# signal3.net
KiCad netlist of a schematic drawn in Altium Designer
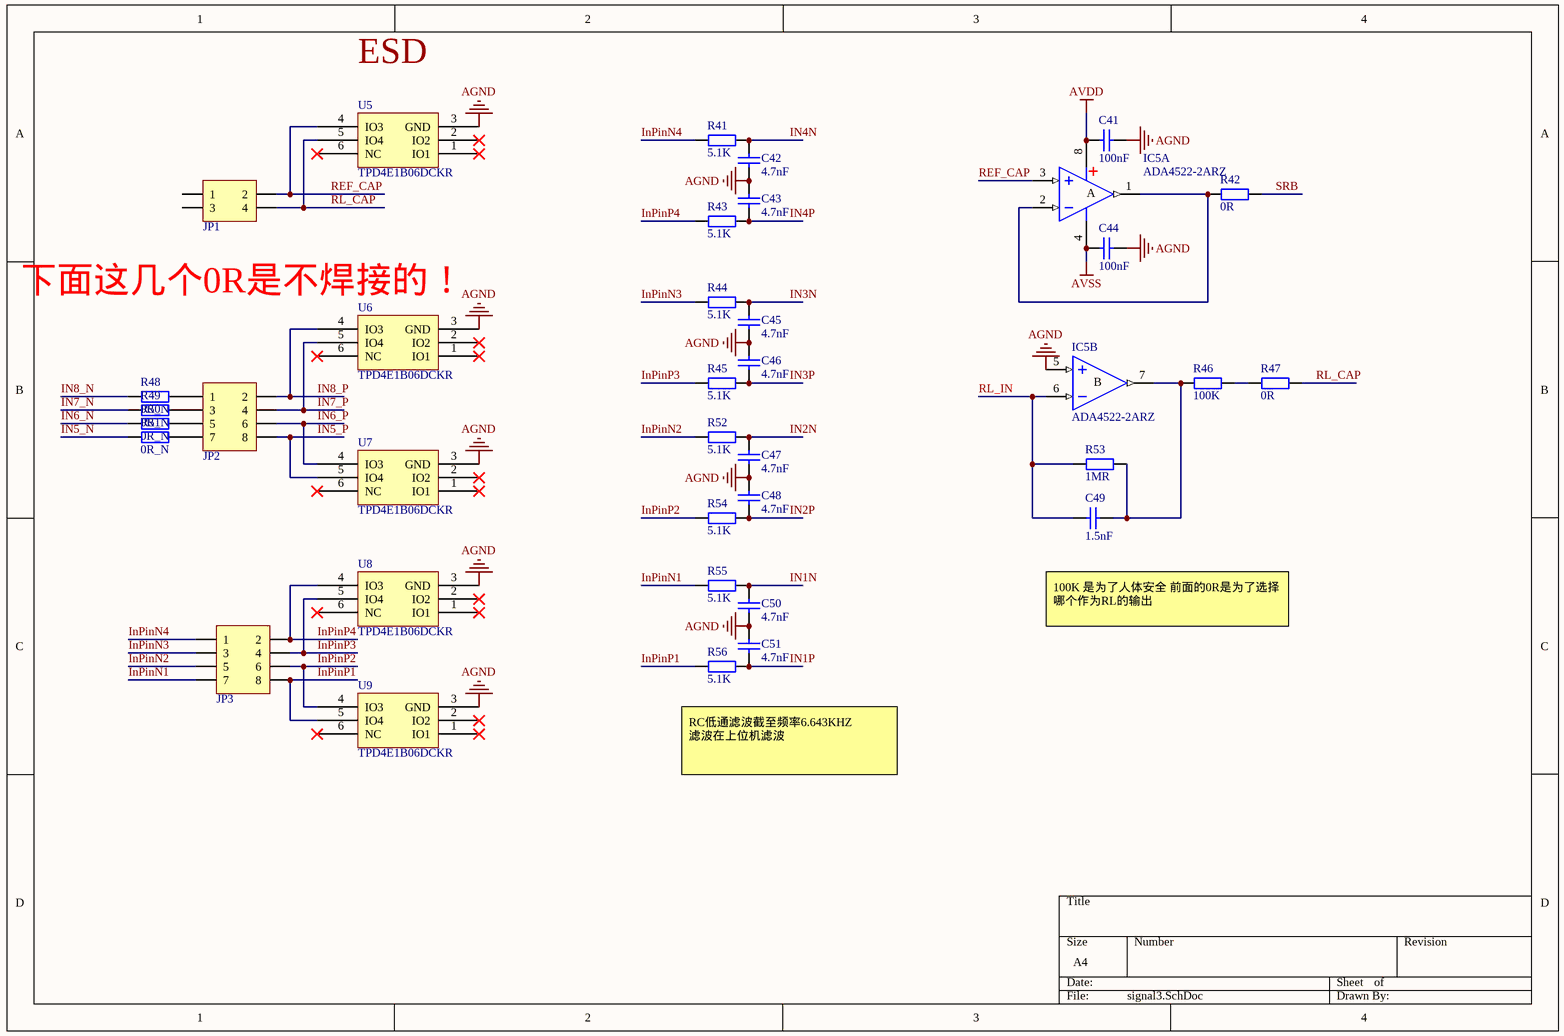
[diagram p0: signal3.SchDoc]

(export (version "E")
  (design (tool "Eeschema 10.0.6"))
  (components
    (comp (ref "C41")
      (value "100nF")
      (footprint "C0603_L")
      (description "贴片电容/MLCC电容")
      (libsource (lib "0.1 - 电阻-电容-电感-保险丝-晶振-晶体-磁珠-电位器-法拉电容-馈通电容") (part "C"))
    )
    (comp (ref "C42")
      (value "4.7nF")
      (footprint "C0603_L")
      (description "贴片电容/MLCC电容")
      (libsource (lib "0.1 - 电阻-电容-电感-保险丝-晶振-晶体-磁珠-电位器-法拉电容-馈通电容") (part "C"))
    )
    (comp (ref "C43")
      (value "4.7nF")
      (footprint "C0603_L")
      (description "贴片电容/MLCC电容")
      (libsource (lib "0.1 - 电阻-电容-电感-保险丝-晶振-晶体-磁珠-电位器-法拉电容-馈通电容") (part "C"))
    )
    (comp (ref "C44")
      (value "100nF")
      (footprint "C0603_L")
      (description "贴片电容/MLCC电容")
      (libsource (lib "0.1 - 电阻-电容-电感-保险丝-晶振-晶体-磁珠-电位器-法拉电容-馈通电容") (part "C"))
    )
    (comp (ref "C45")
      (value "4.7nF")
      (footprint "C0603_L")
      (description "贴片电容/MLCC电容")
      (libsource (lib "0.1 - 电阻-电容-电感-保险丝-晶振-晶体-磁珠-电位器-法拉电容-馈通电容") (part "C"))
    )
    (comp (ref "C46")
      (value "4.7nF")
      (footprint "C0603_L")
      (description "贴片电容/MLCC电容")
      (libsource (lib "0.1 - 电阻-电容-电感-保险丝-晶振-晶体-磁珠-电位器-法拉电容-馈通电容") (part "C"))
    )
    (comp (ref "C47")
      (value "4.7nF")
      (footprint "C0603_L")
      (description "贴片电容/MLCC电容")
      (libsource (lib "0.1 - 电阻-电容-电感-保险丝-晶振-晶体-磁珠-电位器-法拉电容-馈通电容") (part "C"))
    )
    (comp (ref "C48")
      (value "4.7nF")
      (footprint "C0603_L")
      (description "贴片电容/MLCC电容")
      (libsource (lib "0.1 - 电阻-电容-电感-保险丝-晶振-晶体-磁珠-电位器-法拉电容-馈通电容") (part "C"))
    )
    (comp (ref "C49")
      (value "1.5nF")
      (footprint "C0603_L")
      (description "贴片电容/MLCC电容")
      (libsource (lib "0.1 - 电阻-电容-电感-保险丝-晶振-晶体-磁珠-电位器-法拉电容-馈通电容") (part "C"))
    )
    (comp (ref "C50")
      (value "4.7nF")
      (footprint "C0603_L")
      (description "贴片电容/MLCC电容")
      (libsource (lib "0.1 - 电阻-电容-电感-保险丝-晶振-晶体-磁珠-电位器-法拉电容-馈通电容") (part "C"))
    )
    (comp (ref "C51")
      (value "4.7nF")
      (footprint "C0603_L")
      (description "贴片电容/MLCC电容")
      (libsource (lib "0.1 - 电阻-电容-电感-保险丝-晶振-晶体-磁珠-电位器-法拉电容-馈通电容") (part "C"))
    )
    (comp (ref "IC5")
      (value "ADA4522-2ARZ")
      (footprint "SOIC-8")
      (description "双通道55V、EMI增强型、零漂移、超低噪声、RRO运算放大器")
      (libsource (lib "HT") (part "ADA4522-2ARZ"))
    )
    (comp (ref "JP1")
      (value "Header2X2")
      (footprint "HDR2.54-WI-2x2P")
      (description "2*2P接插件")
      (libsource (lib "5.5 - 2.54mm连接器(KF2EDGK_XH2.54_2.54排针排母)") (part "Header 2X2"))
    )
    (comp (ref "JP2")
      (value "Header 4X2")
      (footprint "HDR2.54-WI-2x4P")
      (description "4*2P接插件")
      (libsource (lib "5.5 - 2.54mm连接器(KF2EDGK_XH2.54_2.54排针排母)") (part "Header 4X2"))
    )
    (comp (ref "JP3")
      (value "Header 4X2")
      (footprint "HDR2.54-WI-2x4P")
      (description "4*2P接插件")
      (libsource (lib "5.5 - 2.54mm连接器(KF2EDGK_XH2.54_2.54排针排母)") (part "Header 4X2"))
    )
    (comp (ref "R41")
      (value "5.1K")
      (footprint "R0603_L")
      (description "贴片电阻")
      (libsource (lib "0.1 - 电阻-电容-电感-保险丝-晶振-晶体-磁珠-电位器-法拉电容-馈通电容") (part "R"))
    )
    (comp (ref "R42")
      (value "0R")
      (footprint "R0603_L")
      (description "贴片电阻")
      (libsource (lib "0.1 - 电阻-电容-电感-保险丝-晶振-晶体-磁珠-电位器-法拉电容-馈通电容") (part "R"))
    )
    (comp (ref "R43")
      (value "5.1K")
      (footprint "R0603_L")
      (description "贴片电阻")
      (libsource (lib "0.1 - 电阻-电容-电感-保险丝-晶振-晶体-磁珠-电位器-法拉电容-馈通电容") (part "R"))
    )
    (comp (ref "R44")
      (value "5.1K")
      (footprint "R0603_L")
      (description "贴片电阻")
      (libsource (lib "0.1 - 电阻-电容-电感-保险丝-晶振-晶体-磁珠-电位器-法拉电容-馈通电容") (part "R"))
    )
    (comp (ref "R45")
      (value "5.1K")
      (footprint "R0603_L")
      (description "贴片电阻")
      (libsource (lib "0.1 - 电阻-电容-电感-保险丝-晶振-晶体-磁珠-电位器-法拉电容-馈通电容") (part "R"))
    )
    (comp (ref "R46")
      (value "100K")
      (footprint "R0603_L")
      (description "贴片电阻")
      (libsource (lib "0.1 - 电阻-电容-电感-保险丝-晶振-晶体-磁珠-电位器-法拉电容-馈通电容") (part "R"))
    )
    (comp (ref "R47")
      (value "0R")
      (footprint "R0603_L")
      (description "贴片电阻")
      (libsource (lib "0.1 - 电阻-电容-电感-保险丝-晶振-晶体-磁珠-电位器-法拉电容-馈通电容") (part "R"))
    )
    (comp (ref "R48")
      (value "0R_N")
      (footprint "R0603_L")
      (description "贴片电阻")
      (libsource (lib "0.1 - 电阻-电容-电感-保险丝-晶振-晶体-磁珠-电位器-法拉电容-馈通电容") (part "R"))
    )
    (comp (ref "R49")
      (value "0R_N")
      (footprint "R0603_L")
      (description "贴片电阻")
      (libsource (lib "0.1 - 电阻-电容-电感-保险丝-晶振-晶体-磁珠-电位器-法拉电容-馈通电容") (part "R"))
    )
    (comp (ref "R50")
      (value "0R_N")
      (footprint "R0603_L")
      (description "贴片电阻")
      (libsource (lib "0.1 - 电阻-电容-电感-保险丝-晶振-晶体-磁珠-电位器-法拉电容-馈通电容") (part "R"))
    )
    (comp (ref "R51")
      (value "0R_N")
      (footprint "R0603_L")
      (description "贴片电阻")
      (libsource (lib "0.1 - 电阻-电容-电感-保险丝-晶振-晶体-磁珠-电位器-法拉电容-馈通电容") (part "R"))
    )
    (comp (ref "R52")
      (value "5.1K")
      (footprint "R0603_L")
      (description "贴片电阻")
      (libsource (lib "0.1 - 电阻-电容-电感-保险丝-晶振-晶体-磁珠-电位器-法拉电容-馈通电容") (part "R"))
    )
    (comp (ref "R53")
      (value "1MR")
      (footprint "R0603_L")
      (description "贴片电阻")
      (libsource (lib "0.1 - 电阻-电容-电感-保险丝-晶振-晶体-磁珠-电位器-法拉电容-馈通电容") (part "R"))
    )
    (comp (ref "R54")
      (value "5.1K")
      (footprint "R0603_L")
      (description "贴片电阻")
      (libsource (lib "0.1 - 电阻-电容-电感-保险丝-晶振-晶体-磁珠-电位器-法拉电容-馈通电容") (part "R"))
    )
    (comp (ref "R55")
      (value "5.1K")
      (footprint "R0603_L")
      (description "贴片电阻")
      (libsource (lib "0.1 - 电阻-电容-电感-保险丝-晶振-晶体-磁珠-电位器-法拉电容-馈通电容") (part "R"))
    )
    (comp (ref "R56")
      (value "5.1K")
      (footprint "R0603_L")
      (description "贴片电阻")
      (libsource (lib "0.1 - 电阻-电容-电感-保险丝-晶振-晶体-磁珠-电位器-法拉电容-馈通电容") (part "R"))
    )
    (comp (ref "U5")
      (value "TPD4E1B06DCKR")
      (footprint "SOT363_N")
      (description "具有 0.5nA 最大泄漏电流的四路 0.7pF、±5.5V、±12kV ESD 保护二极管")
      (libsource (lib "HT") (part "TPD4E1B06DCKR"))
    )
    (comp (ref "U6")
      (value "TPD4E1B06DCKR")
      (footprint "SOT363_N")
      (description "具有 0.5nA 最大泄漏电流的四路 0.7pF、±5.5V、±12kV ESD 保护二极管")
      (libsource (lib "HT") (part "TPD4E1B06DCKR"))
    )
    (comp (ref "U7")
      (value "TPD4E1B06DCKR")
      (footprint "SOT363_N")
      (description "具有 0.5nA 最大泄漏电流的四路 0.7pF、±5.5V、±12kV ESD 保护二极管")
      (libsource (lib "HT") (part "TPD4E1B06DCKR"))
    )
    (comp (ref "U8")
      (value "TPD4E1B06DCKR")
      (footprint "SOT363_N")
      (description "具有 0.5nA 最大泄漏电流的四路 0.7pF、±5.5V、±12kV ESD 保护二极管")
      (libsource (lib "HT") (part "TPD4E1B06DCKR"))
    )
    (comp (ref "U9")
      (value "TPD4E1B06DCKR")
      (footprint "SOT363_N")
      (description "具有 0.5nA 最大泄漏电流的四路 0.7pF、±5.5V、±12kV ESD 保护二极管")
      (libsource (lib "HT") (part "TPD4E1B06DCKR"))
    )
  )
  (nets
    (net (code "1") (name "/IN1N") (class "Default")
      (node (ref "C50") (pin "2") (pinfunction "2_2") (pintype "passive"))
      (node (ref "R55") (pin "2") (pinfunction "2_2") (pintype "passive"))
    )
    (net (code "2") (name "/IN1P") (class "Default")
      (node (ref "C51") (pin "1") (pinfunction "1_1") (pintype "passive"))
      (node (ref "R56") (pin "2") (pinfunction "2_2") (pintype "passive"))
    )
    (net (code "3") (name "/IN2N") (class "Default")
      (node (ref "C47") (pin "2") (pinfunction "2_2") (pintype "passive"))
      (node (ref "R52") (pin "2") (pinfunction "2_2") (pintype "passive"))
    )
    (net (code "4") (name "/IN2P") (class "Default")
      (node (ref "C48") (pin "1") (pinfunction "1_1") (pintype "passive"))
      (node (ref "R54") (pin "2") (pinfunction "2_2") (pintype "passive"))
    )
    (net (code "5") (name "/IN3N") (class "Default")
      (node (ref "C45") (pin "2") (pinfunction "2_2") (pintype "passive"))
      (node (ref "R44") (pin "2") (pinfunction "2_2") (pintype "passive"))
    )
    (net (code "6") (name "/IN3P") (class "Default")
      (node (ref "C46") (pin "1") (pinfunction "1_1") (pintype "passive"))
      (node (ref "R45") (pin "2") (pinfunction "2_2") (pintype "passive"))
    )
    (net (code "7") (name "/IN4N") (class "Default")
      (node (ref "C42") (pin "2") (pinfunction "2_2") (pintype "passive"))
      (node (ref "R41") (pin "2") (pinfunction "2_2") (pintype "passive"))
    )
    (net (code "8") (name "/IN4P") (class "Default")
      (node (ref "C43") (pin "1") (pinfunction "1_1") (pintype "passive"))
      (node (ref "R43") (pin "2") (pinfunction "2_2") (pintype "passive"))
    )
    (net (code "9") (name "/IN5_N") (class "Default")
      (node (ref "R51") (pin "2") (pinfunction "2_2") (pintype "passive"))
    )
    (net (code "10") (name "/IN5_P") (class "Default")
      (node (ref "JP2") (pin "8") (pinfunction "8_8") (pintype "passive"))
      (node (ref "U7") (pin "5") (pinfunction "IO4_5") (pintype "passive"))
    )
    (net (code "11") (name "/IN6_N") (class "Default")
      (node (ref "R50") (pin "2") (pinfunction "2_2") (pintype "passive"))
    )
    (net (code "12") (name "/IN6_P") (class "Default")
      (node (ref "JP2") (pin "6") (pinfunction "6_6") (pintype "passive"))
      (node (ref "U7") (pin "4") (pinfunction "IO3_4") (pintype "passive"))
    )
    (net (code "13") (name "/IN7_N") (class "Default")
      (node (ref "R49") (pin "2") (pinfunction "2_2") (pintype "passive"))
    )
    (net (code "14") (name "/IN7_P") (class "Default")
      (node (ref "JP2") (pin "4") (pinfunction "4_4") (pintype "passive"))
      (node (ref "U6") (pin "5") (pinfunction "IO4_5") (pintype "passive"))
    )
    (net (code "15") (name "/IN8_N") (class "Default")
      (node (ref "R48") (pin "2") (pinfunction "2_2") (pintype "passive"))
    )
    (net (code "16") (name "/IN8_P") (class "Default")
      (node (ref "JP2") (pin "2") (pinfunction "2_2") (pintype "passive"))
      (node (ref "U6") (pin "4") (pinfunction "IO3_4") (pintype "passive"))
    )
    (net (code "17") (name "/InPinN1") (class "Default")
      (node (ref "JP3") (pin "7") (pinfunction "7_7") (pintype "passive"))
      (node (ref "R55") (pin "1") (pinfunction "1_1") (pintype "passive"))
    )
    (net (code "18") (name "/InPinN2") (class "Default")
      (node (ref "JP3") (pin "5") (pinfunction "5_5") (pintype "passive"))
      (node (ref "R52") (pin "1") (pinfunction "1_1") (pintype "passive"))
    )
    (net (code "19") (name "/InPinN3") (class "Default")
      (node (ref "JP3") (pin "3") (pinfunction "3_3") (pintype "passive"))
      (node (ref "R44") (pin "1") (pinfunction "1_1") (pintype "passive"))
    )
    (net (code "20") (name "/InPinN4") (class "Default")
      (node (ref "JP3") (pin "1") (pinfunction "1_1") (pintype "passive"))
      (node (ref "R41") (pin "1") (pinfunction "1_1") (pintype "passive"))
    )
    (net (code "21") (name "/InPinP1") (class "Default")
      (node (ref "JP3") (pin "8") (pinfunction "8_8") (pintype "passive"))
      (node (ref "R56") (pin "1") (pinfunction "1_1") (pintype "passive"))
      (node (ref "U9") (pin "5") (pinfunction "IO4_5") (pintype "passive"))
    )
    (net (code "22") (name "/InPinP2") (class "Default")
      (node (ref "JP3") (pin "6") (pinfunction "6_6") (pintype "passive"))
      (node (ref "R54") (pin "1") (pinfunction "1_1") (pintype "passive"))
      (node (ref "U9") (pin "4") (pinfunction "IO3_4") (pintype "passive"))
    )
    (net (code "23") (name "/InPinP3") (class "Default")
      (node (ref "JP3") (pin "4") (pinfunction "4_4") (pintype "passive"))
      (node (ref "R45") (pin "1") (pinfunction "1_1") (pintype "passive"))
      (node (ref "U8") (pin "5") (pinfunction "IO4_5") (pintype "passive"))
    )
    (net (code "24") (name "/InPinP4") (class "Default")
      (node (ref "JP3") (pin "2") (pinfunction "2_2") (pintype "passive"))
      (node (ref "R43") (pin "1") (pinfunction "1_1") (pintype "passive"))
      (node (ref "U8") (pin "4") (pinfunction "IO3_4") (pintype "passive"))
    )
    (net (code "25") (name "/REF_CAP") (class "Default")
      (node (ref "IC5") (pin "3") (pinfunction "IN+_3") (pintype "input"))
      (node (ref "JP1") (pin "2") (pinfunction "2_2") (pintype "passive"))
      (node (ref "U5") (pin "4") (pinfunction "IO3_4") (pintype "passive"))
    )
    (net (code "26") (name "/RL_CAP") (class "Default")
      (node (ref "JP1") (pin "4") (pinfunction "4_4") (pintype "passive"))
      (node (ref "R47") (pin "1") (pinfunction "1_1") (pintype "passive"))
      (node (ref "U5") (pin "5") (pinfunction "IO4_5") (pintype "passive"))
    )
    (net (code "27") (name "/RL_IN") (class "Default")
      (node (ref "C49") (pin "1") (pinfunction "1_1") (pintype "passive"))
      (node (ref "IC5") (pin "6") (pinfunction "IN-_6") (pintype "input"))
      (node (ref "R53") (pin "2") (pinfunction "2_2") (pintype "passive"))
    )
    (net (code "28") (name "/SRB") (class "Default")
      (node (ref "R42") (pin "1") (pinfunction "1_1") (pintype "passive"))
    )
    (net (code "29") (name "AGND") (class "Default")
      (node (ref "C41") (pin "2") (pinfunction "2_2") (pintype "passive"))
      (node (ref "C42") (pin "1") (pinfunction "1_1") (pintype "passive"))
      (node (ref "C43") (pin "2") (pinfunction "2_2") (pintype "passive"))
      (node (ref "C44") (pin "2") (pinfunction "2_2") (pintype "passive"))
      (node (ref "C45") (pin "1") (pinfunction "1_1") (pintype "passive"))
      (node (ref "C46") (pin "2") (pinfunction "2_2") (pintype "passive"))
      (node (ref "C47") (pin "1") (pinfunction "1_1") (pintype "passive"))
      (node (ref "C48") (pin "2") (pinfunction "2_2") (pintype "passive"))
      (node (ref "C50") (pin "1") (pinfunction "1_1") (pintype "passive"))
      (node (ref "C51") (pin "2") (pinfunction "2_2") (pintype "passive"))
      (node (ref "IC5") (pin "5") (pinfunction "IN+_5") (pintype "input"))
      (node (ref "U5") (pin "3") (pinfunction "GND_3") (pintype "passive"))
      (node (ref "U6") (pin "3") (pinfunction "GND_3") (pintype "passive"))
      (node (ref "U7") (pin "3") (pinfunction "GND_3") (pintype "passive"))
      (node (ref "U8") (pin "3") (pinfunction "GND_3") (pintype "passive"))
      (node (ref "U9") (pin "3") (pinfunction "GND_3") (pintype "passive"))
    )
    (net (code "30") (name "AVDD") (class "Default")
      (node (ref "C41") (pin "1") (pinfunction "1_1") (pintype "passive"))
      (node (ref "IC5") (pin "8") (pinfunction "V+_8") (pintype "power_in"))
    )
    (net (code "31") (name "AVSS") (class "Default")
      (node (ref "C44") (pin "1") (pinfunction "1_1") (pintype "passive"))
      (node (ref "IC5") (pin "4") (pinfunction "V-_4") (pintype "power_in"))
    )
    (net (code "32") (name "Net-(IC5A-IN-)") (class "Default")
      (node (ref "IC5") (pin "1") (pinfunction "OUT_1") (pintype "output"))
      (node (ref "IC5") (pin "2") (pinfunction "IN-_2") (pintype "input"))
      (node (ref "R42") (pin "2") (pinfunction "2_2") (pintype "passive"))
    )
    (net (code "33") (name "Net-(IC5B-OUT)") (class "Default")
      (node (ref "C49") (pin "2") (pinfunction "2_2") (pintype "passive"))
      (node (ref "IC5") (pin "7") (pinfunction "OUT_7") (pintype "output"))
      (node (ref "R46") (pin "2") (pinfunction "2_2") (pintype "passive"))
      (node (ref "R53") (pin "1") (pinfunction "1_1") (pintype "passive"))
    )
    (net (code "34") (name "Net-(JP2-Pad1)") (class "Default")
      (node (ref "JP2") (pin "1") (pinfunction "1_1") (pintype "passive"))
      (node (ref "R48") (pin "1") (pinfunction "1_1") (pintype "passive"))
    )
    (net (code "35") (name "Net-(JP2-Pad3)") (class "Default")
      (node (ref "JP2") (pin "3") (pinfunction "3_3") (pintype "passive"))
      (node (ref "R49") (pin "1") (pinfunction "1_1") (pintype "passive"))
    )
    (net (code "36") (name "Net-(JP2-Pad5)") (class "Default")
      (node (ref "JP2") (pin "5") (pinfunction "5_5") (pintype "passive"))
      (node (ref "R50") (pin "1") (pinfunction "1_1") (pintype "passive"))
    )
    (net (code "37") (name "Net-(JP2-Pad7)") (class "Default")
      (node (ref "JP2") (pin "7") (pinfunction "7_7") (pintype "passive"))
      (node (ref "R51") (pin "1") (pinfunction "1_1") (pintype "passive"))
    )
    (net (code "38") (name "Net-(R46-Pad1)") (class "Default")
      (node (ref "R46") (pin "1") (pinfunction "1_1") (pintype "passive"))
      (node (ref "R47") (pin "2") (pinfunction "2_2") (pintype "passive"))
    )
    (net (code "39") (name "unconnected-(JP1-Pad1)") (class "Default")
      (node (ref "JP1") (pin "1") (pinfunction "1_1") (pintype "passive"))
    )
    (net (code "40") (name "unconnected-(JP1-Pad3)") (class "Default")
      (node (ref "JP1") (pin "3") (pinfunction "3_3") (pintype "passive"))
    )
    (net (code "41") (name "unconnected-(U5-IO1-Pad1)") (class "Default")
      (node (ref "U5") (pin "1") (pinfunction "IO1_1") (pintype "passive+no_connect"))
    )
    (net (code "42") (name "unconnected-(U5-IO2-Pad2)") (class "Default")
      (node (ref "U5") (pin "2") (pinfunction "IO2_2") (pintype "passive+no_connect"))
    )
    (net (code "43") (name "unconnected-(U5-NC-Pad6)") (class "Default")
      (node (ref "U5") (pin "6") (pinfunction "NC_6") (pintype "passive+no_connect"))
    )
    (net (code "44") (name "unconnected-(U6-IO1-Pad1)") (class "Default")
      (node (ref "U6") (pin "1") (pinfunction "IO1_1") (pintype "passive+no_connect"))
    )
    (net (code "45") (name "unconnected-(U6-IO2-Pad2)") (class "Default")
      (node (ref "U6") (pin "2") (pinfunction "IO2_2") (pintype "passive+no_connect"))
    )
    (net (code "46") (name "unconnected-(U6-NC-Pad6)") (class "Default")
      (node (ref "U6") (pin "6") (pinfunction "NC_6") (pintype "passive+no_connect"))
    )
    (net (code "47") (name "unconnected-(U7-IO1-Pad1)") (class "Default")
      (node (ref "U7") (pin "1") (pinfunction "IO1_1") (pintype "passive+no_connect"))
    )
    (net (code "48") (name "unconnected-(U7-IO2-Pad2)") (class "Default")
      (node (ref "U7") (pin "2") (pinfunction "IO2_2") (pintype "passive+no_connect"))
    )
    (net (code "49") (name "unconnected-(U7-NC-Pad6)") (class "Default")
      (node (ref "U7") (pin "6") (pinfunction "NC_6") (pintype "passive+no_connect"))
    )
    (net (code "50") (name "unconnected-(U8-IO1-Pad1)") (class "Default")
      (node (ref "U8") (pin "1") (pinfunction "IO1_1") (pintype "passive+no_connect"))
    )
    (net (code "51") (name "unconnected-(U8-IO2-Pad2)") (class "Default")
      (node (ref "U8") (pin "2") (pinfunction "IO2_2") (pintype "passive+no_connect"))
    )
    (net (code "52") (name "unconnected-(U8-NC-Pad6)") (class "Default")
      (node (ref "U8") (pin "6") (pinfunction "NC_6") (pintype "passive+no_connect"))
    )
    (net (code "53") (name "unconnected-(U9-IO1-Pad1)") (class "Default")
      (node (ref "U9") (pin "1") (pinfunction "IO1_1") (pintype "passive+no_connect"))
    )
    (net (code "54") (name "unconnected-(U9-IO2-Pad2)") (class "Default")
      (node (ref "U9") (pin "2") (pinfunction "IO2_2") (pintype "passive+no_connect"))
    )
    (net (code "55") (name "unconnected-(U9-NC-Pad6)") (class "Default")
      (node (ref "U9") (pin "6") (pinfunction "NC_6") (pintype "passive+no_connect"))
    )
  )
)
